# Esp8266-01_PACSSol.net
KiCad netlist of a schematic drawn in EAGLE
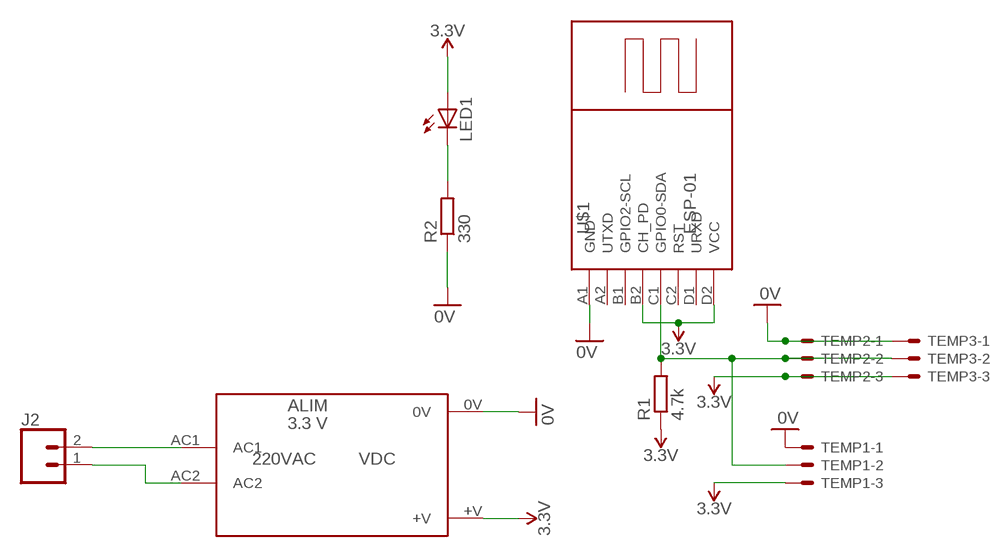
[diagram p0: schematic, sheet 1]

(export (version "E")
  (design (tool "Eeschema 10.0.6"))
  (components
    (comp (ref "ALIM")
      (value "3.3 V")
      (footprint "eagle-import:TSP05-VDC-3W")
      (libsource (lib "eagle-import") (part "TSP05-5V-3W"))
    )
    (comp (ref "J2")
      (value "CONN_025MM")
      (footprint "eagle-import:BORNIER_A_VIS_2_5.12MM")
      (libsource (lib "eagle-import") (part "CONN_025MM"))
    )
    (comp (ref "LED1")
      (value "LED5MM_F")
      (footprint "eagle-import:LED5MM")
      (libsource (lib "eagle-import") (part "LED5MM_F"))
    )
    (comp (ref "R1")
      (value "4.7k")
      (footprint "eagle-import:0207_10")
      (libsource (lib "eagle-import") (part "R-EU_0207/10"))
    )
    (comp (ref "R2")
      (value "330")
      (footprint "eagle-import:0207_10")
      (libsource (lib "eagle-import") (part "R-EU_0207/10"))
    )
    (comp (ref "TEMP1")
      (value "JST-XH-03-PIN-LONG-PAD")
      (footprint "eagle-import:JST-XH-03-PACKAGE-LONG-PAD")
      (libsource (lib "eagle-import") (part "JST-XH-03-PIN-LONG-PAD"))
    )
    (comp (ref "TEMP2")
      (value "JST-XH-03-PIN-LONG-PAD")
      (footprint "eagle-import:JST-XH-03-PACKAGE-LONG-PAD")
      (libsource (lib "eagle-import") (part "JST-XH-03-PIN-LONG-PAD"))
    )
    (comp (ref "TEMP3")
      (value "JST-XH-03-PIN-LONG-PAD")
      (footprint "eagle-import:JST-XH-03-PACKAGE-LONG-PAD")
      (libsource (lib "eagle-import") (part "JST-XH-03-PIN-LONG-PAD"))
    )
    (comp (ref "U$1")
      (value "ESP-01")
      (footprint "eagle-import:ESP-01")
      (libsource (lib "eagle-import") (part "ESP-01"))
    )
  )
  (nets
    (net (code "1") (name "0V") (class "Default")
      (node (ref "ALIM") (pin "0V") (pinfunction "0V_0V") (pintype "output"))
      (node (ref "R2") (pin "1") (pinfunction "1_1") (pintype "passive"))
      (node (ref "TEMP1") (pin "1") (pinfunction "S_1") (pintype "passive"))
      (node (ref "TEMP2") (pin "1") (pinfunction "S_1") (pintype "passive"))
      (node (ref "TEMP3") (pin "1") (pinfunction "S_1") (pintype "passive"))
      (node (ref "U$1") (pin "A1") (pinfunction "GND_A1") (pintype "power_in"))
    )
    (net (code "2") (name "3.3V") (class "Default")
      (node (ref "ALIM") (pin "+V") (pinfunction "+V_+V") (pintype "output"))
      (node (ref "LED1") (pin "A") (pinfunction "A_A") (pintype "passive"))
      (node (ref "R1") (pin "1") (pinfunction "1_1") (pintype "passive"))
      (node (ref "TEMP1") (pin "3") (pinfunction "S_3") (pintype "passive"))
      (node (ref "TEMP2") (pin "3") (pinfunction "S_3") (pintype "passive"))
      (node (ref "TEMP3") (pin "3") (pinfunction "S_3") (pintype "passive"))
      (node (ref "U$1") (pin "B2") (pinfunction "CH_PD_B2") (pintype "bidirectional"))
      (node (ref "U$1") (pin "D2") (pinfunction "VCC_D2") (pintype "power_in"))
    )
    (net (code "3") (name "Net-(ALIM-PadAC1)") (class "Default")
      (node (ref "ALIM") (pin "AC1") (pinfunction "AC1_AC1") (pintype "bidirectional"))
      (node (ref "J2") (pin "2") (pinfunction "2_2") (pintype "passive"))
    )
    (net (code "4") (name "Net-(ALIM-PadAC2)") (class "Default")
      (node (ref "ALIM") (pin "AC2") (pinfunction "AC2_AC2") (pintype "input"))
      (node (ref "J2") (pin "1") (pinfunction "1_1") (pintype "passive"))
    )
    (net (code "5") (name "Net-(LED1-C)") (class "Default")
      (node (ref "LED1") (pin "K") (pinfunction "C_K") (pintype "passive"))
      (node (ref "R2") (pin "2") (pinfunction "2_2") (pintype "passive"))
    )
    (net (code "6") (name "Net-(TEMP1B-S)") (class "Default")
      (node (ref "R1") (pin "2") (pinfunction "2_2") (pintype "passive"))
      (node (ref "TEMP1") (pin "2") (pinfunction "S_2") (pintype "passive"))
      (node (ref "TEMP2") (pin "2") (pinfunction "S_2") (pintype "passive"))
      (node (ref "TEMP3") (pin "2") (pinfunction "S_2") (pintype "passive"))
      (node (ref "U$1") (pin "C1") (pinfunction "GPIO0-SDA_C1") (pintype "bidirectional"))
    )
    (net (code "7") (name "unconnected-(U$1-GPIO2-SCL-PadB1)") (class "Default")
      (node (ref "U$1") (pin "B1") (pinfunction "GPIO2-SCL_B1") (pintype "bidirectional"))
    )
    (net (code "8") (name "unconnected-(U$1-RST-PadC2)") (class "Default")
      (node (ref "U$1") (pin "C2") (pinfunction "RST_C2") (pintype "bidirectional"))
    )
    (net (code "9") (name "unconnected-(U$1-URXD-PadD1)") (class "Default")
      (node (ref "U$1") (pin "D1") (pinfunction "URXD_D1") (pintype "bidirectional"))
    )
    (net (code "10") (name "unconnected-(U$1-UTXD-PadA2)") (class "Default")
      (node (ref "U$1") (pin "A2") (pinfunction "UTXD_A2") (pintype "bidirectional"))
    )
  )
)
